# STM32.net
KiCad netlist of a schematic drawn in Altium Designer
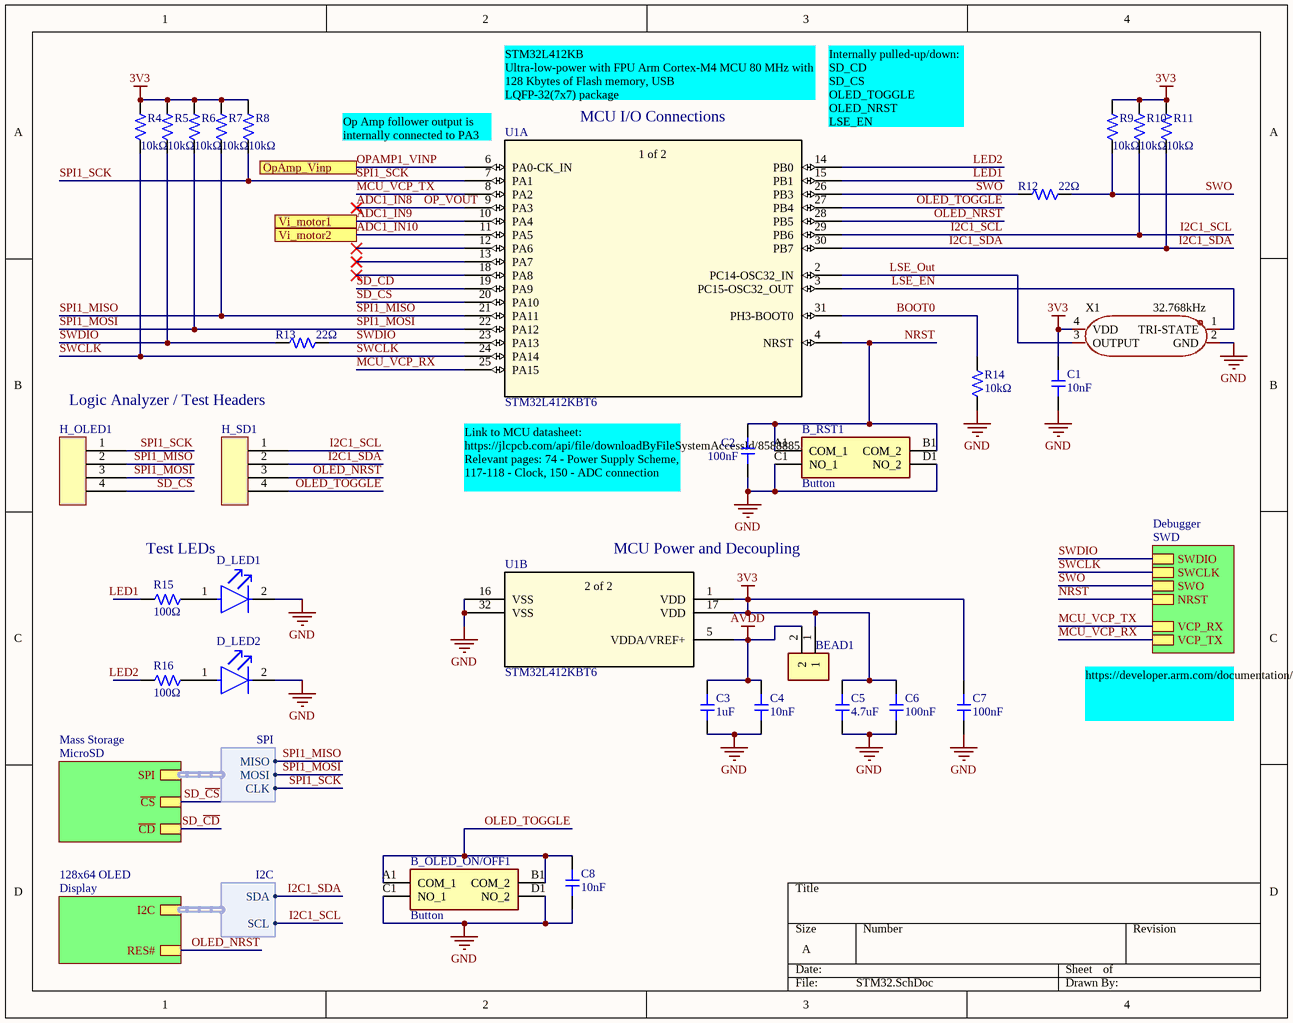
[diagram p0: STM32.SchDoc]

(export (version "E")
  (design (tool "Eeschema 10.0.6"))
  (components
    (comp (ref "BEAD1")
      (value "GZ1608D601TF")
      (footprint "SamacSys:BEADC1608X95N")
      (description "Ferrite Bead")
      (libsource (lib "SamacSys") (part "GZ1608D601TF"))
    )
    (comp (ref "B_OLED_ON/OFF1")
      (value "Button")
      (footprint "SamacSys:TS1187ABAB")
      (fields (field (name "MANUFACTURER_PART_NUMBER") "TS-1187A-B-A-B"))
      (libsource (lib "SamacSys") (part "TS-1187A-B-A-B"))
    )
    (comp (ref "B_RST1")
      (value "Button")
      (footprint "SamacSys:TS1187ABAB")
      (fields (field (name "MANUFACTURER_PART_NUMBER") "TS-1187A-B-A-B"))
      (libsource (lib "SamacSys") (part "TS-1187A-B-A-B"))
    )
    (comp (ref "C1")
      (value "CL05B103KB5NNNC")
      (footprint "CAP-0402")
      (description "Capacitor, Ceramic (MLCC), 10nF, ±10%, 50V, X7R, ±10%, SMD 0402")
      (fields
        (field (name "JLCPCB BASIC PART") "Yes")
        (field (name "CAPACITANCE") "10nF")
        (field (name "JLCPCB PART NUMBER") "C15195")
      )
      (libsource (lib "jlcpcb_2024_10_capacitors_basic") (part "CL05B103KB5NNNC"))
    )
    (comp (ref "C2")
      (value "CL05B104KB54PNC")
      (footprint "CAP-0402")
      (description "Capacitor, Ceramic (MLCC), 100nF, ±10%, 50V, X7R, ±10%, SMD 0402")
      (fields
        (field (name "JLCPCB BASIC PART") "Yes")
        (field (name "CAPACITANCE") "100nF")
        (field (name "JLCPCB PART NUMBER") "C307331")
      )
      (libsource (lib "jlcpcb_2024_10_capacitors_basic") (part "CL05B104KB54PNC"))
    )
    (comp (ref "C3")
      (value "CL05A105KA5NQNC")
      (footprint "CAP-0402")
      (description "Capacitor, Ceramic (MLCC), 1uF, ±10%, 25V, X5R, ±10%, SMD 0402")
      (fields
        (field (name "JLCPCB BASIC PART") "Yes")
        (field (name "CAPACITANCE") "1uF")
        (field (name "JLCPCB PART NUMBER") "C52923")
      )
      (libsource (lib "jlcpcb_2024_10_capacitors_basic") (part "CL05A105KA5NQNC"))
    )
    (comp (ref "C4")
      (value "CL05B103KB5NNNC")
      (footprint "CAP-0402")
      (description "Capacitor, Ceramic (MLCC), 10nF, ±10%, 50V, X7R, ±10%, SMD 0402")
      (fields
        (field (name "JLCPCB BASIC PART") "Yes")
        (field (name "CAPACITANCE") "10nF")
        (field (name "JLCPCB PART NUMBER") "C15195")
      )
      (libsource (lib "jlcpcb_2024_10_capacitors_basic") (part "CL05B103KB5NNNC"))
    )
    (comp (ref "C5")
      (value "CL05A475MP5NRNC")
      (footprint "CAP-0402")
      (description "Capacitor, Ceramic (MLCC), 4.7uF, ±20%, 10V, X5R, ±20%, SMD 0402")
      (fields
        (field (name "JLCPCB BASIC PART") "Yes")
        (field (name "CAPACITANCE") "4.7uF")
        (field (name "JLCPCB PART NUMBER") "C23733")
      )
      (libsource (lib "jlcpcb_2024_10_capacitors_basic") (part "CL05A475MP5NRNC"))
    )
    (comp (ref "C6")
      (value "CL05B104KO5NNNC")
      (footprint "CAP-0402")
      (description "Capacitor, Ceramic (MLCC), 100nF, ±10%, 16V, X7R, ±10%, SMD 0402")
      (fields
        (field (name "JLCPCB BASIC PART") "Yes")
        (field (name "CAPACITANCE") "100nF")
        (field (name "JLCPCB PART NUMBER") "C1525")
      )
      (libsource (lib "jlcpcb_2024_10_capacitors_basic") (part "CL05B104KO5NNNC"))
    )
    (comp (ref "C7")
      (value "CL05B104KO5NNNC")
      (footprint "CAP-0402")
      (description "Capacitor, Ceramic (MLCC), 100nF, ±10%, 16V, X7R, ±10%, SMD 0402")
      (fields
        (field (name "JLCPCB BASIC PART") "Yes")
        (field (name "CAPACITANCE") "100nF")
        (field (name "JLCPCB PART NUMBER") "C1525")
      )
      (libsource (lib "jlcpcb_2024_10_capacitors_basic") (part "CL05B104KO5NNNC"))
    )
    (comp (ref "C8")
      (value "CL05B103KB5NNNC")
      (footprint "CAP-0402")
      (description "Capacitor, Ceramic (MLCC), 10nF, ±10%, 50V, X7R, ±10%, SMD 0402")
      (fields
        (field (name "JLCPCB BASIC PART") "Yes")
        (field (name "CAPACITANCE") "10nF")
        (field (name "JLCPCB PART NUMBER") "C15195")
      )
      (libsource (lib "jlcpcb_2024_10_capacitors_basic") (part "CL05B103KB5NNNC"))
    )
    (comp (ref "D_LED1")
      (value "~")
      (footprint "FP-AP2012EC-MFG")
      (description "LED RED CLEAR SMD")
      (libsource (lib "Red-LED - 01.02.26 - 14") (part "CMP-44529-000070-1"))
    )
    (comp (ref "D_LED2")
      (value "~")
      (footprint "FP-AP2012EC-MFG")
      (description "LED RED CLEAR SMD")
      (libsource (lib "Red-LED - 01.02.26 - 14") (part "ab1c01a81903e929fc6c44469aada92"))
    )
    (comp (ref "H_OLED1")
      (value "4-pin Header")
      (footprint "4-pin Header")
      (description "4-pin Header 0.1mm pitch")
      (libsource (lib "Schlib1") (part "4-pin Header"))
    )
    (comp (ref "H_SD1")
      (value "4-pin Header")
      (footprint "4-pin Header")
      (description "4-pin Header 0.1mm pitch")
      (libsource (lib "Schlib1") (part "4-pin Header"))
    )
    (comp (ref "R4")
      (value "0402WGF1002TCE")
      (footprint "RES-0402")
      (description "Resistor, 10kΩ, ±1%, 62.5mW, 50V, ±100ppm/℃, -55℃~+155℃, SMD 0402")
      (fields
        (field (name "MANUFACTURER") "Uniroyal")
        (field (name "JLCPCB PART NUMBER") "C25744")
        (field (name "RESISTANCE") "10kΩ")
      )
      (libsource (lib "jlcpcb_2024_10_resistors_basic") (part "0402WGF1002TCE"))
    )
    (comp (ref "R5")
      (value "0402WGF1002TCE")
      (footprint "RES-0402")
      (description "Resistor, 10kΩ, ±1%, 62.5mW, 50V, ±100ppm/℃, -55℃~+155℃, SMD 0402")
      (fields
        (field (name "MANUFACTURER") "Uniroyal")
        (field (name "JLCPCB PART NUMBER") "C25744")
        (field (name "RESISTANCE") "10kΩ")
      )
      (libsource (lib "jlcpcb_2024_10_resistors_basic") (part "0402WGF1002TCE"))
    )
    (comp (ref "R6")
      (value "0402WGF1002TCE")
      (footprint "RES-0402")
      (description "Resistor, 10kΩ, ±1%, 62.5mW, 50V, ±100ppm/℃, -55℃~+155℃, SMD 0402")
      (fields
        (field (name "MANUFACTURER") "Uniroyal")
        (field (name "JLCPCB PART NUMBER") "C25744")
        (field (name "RESISTANCE") "10kΩ")
      )
      (libsource (lib "jlcpcb_2024_10_resistors_basic") (part "0402WGF1002TCE"))
    )
    (comp (ref "R7")
      (value "0402WGF1002TCE")
      (footprint "RES-0402")
      (description "Resistor, 10kΩ, ±1%, 62.5mW, 50V, ±100ppm/℃, -55℃~+155℃, SMD 0402")
      (fields
        (field (name "MANUFACTURER") "Uniroyal")
        (field (name "JLCPCB PART NUMBER") "C25744")
        (field (name "RESISTANCE") "10kΩ")
      )
      (libsource (lib "jlcpcb_2024_10_resistors_basic") (part "0402WGF1002TCE"))
    )
    (comp (ref "R8")
      (value "0402WGF1002TCE")
      (footprint "RES-0402")
      (description "Resistor, 10kΩ, ±1%, 62.5mW, 50V, ±100ppm/℃, -55℃~+155℃, SMD 0402")
      (fields
        (field (name "MANUFACTURER") "Uniroyal")
        (field (name "JLCPCB PART NUMBER") "C25744")
        (field (name "RESISTANCE") "10kΩ")
      )
      (libsource (lib "jlcpcb_2024_10_resistors_basic") (part "0402WGF1002TCE"))
    )
    (comp (ref "R9")
      (value "0402WGF1002TCE")
      (footprint "RES-0402")
      (description "Resistor, 10kΩ, ±1%, 62.5mW, 50V, ±100ppm/℃, -55℃~+155℃, SMD 0402")
      (fields
        (field (name "MANUFACTURER") "Uniroyal")
        (field (name "JLCPCB PART NUMBER") "C25744")
        (field (name "RESISTANCE") "10kΩ")
      )
      (libsource (lib "jlcpcb_2024_10_resistors_basic") (part "0402WGF1002TCE"))
    )
    (comp (ref "R10")
      (value "0402WGF1002TCE")
      (footprint "RES-0402")
      (description "Resistor, 10kΩ, ±1%, 62.5mW, 50V, ±100ppm/℃, -55℃~+155℃, SMD 0402")
      (fields
        (field (name "MANUFACTURER") "Uniroyal")
        (field (name "JLCPCB PART NUMBER") "C25744")
        (field (name "RESISTANCE") "10kΩ")
      )
      (libsource (lib "jlcpcb_2024_10_resistors_basic") (part "0402WGF1002TCE"))
    )
    (comp (ref "R11")
      (value "0402WGF1002TCE")
      (footprint "RES-0402")
      (description "Resistor, 10kΩ, ±1%, 62.5mW, 50V, ±100ppm/℃, -55℃~+155℃, SMD 0402")
      (fields
        (field (name "MANUFACTURER") "Uniroyal")
        (field (name "JLCPCB PART NUMBER") "C25744")
        (field (name "RESISTANCE") "10kΩ")
      )
      (libsource (lib "jlcpcb_2024_10_resistors_basic") (part "0402WGF1002TCE"))
    )
    (comp (ref "R12")
      (value "0402WGF220JTCE")
      (footprint "RES-0402")
      (description "Resistor, 22Ω, ±1%, 62.5mW, 50V, ±200ppm/℃, -55℃~+155℃, SMD 0402")
      (fields
        (field (name "MANUFACTURER") "Uniroyal")
        (field (name "JLCPCB PART NUMBER") "C25092")
        (field (name "RESISTANCE") "22Ω")
      )
      (libsource (lib "jlcpcb_2024_10_resistors_basic") (part "0402WGF220JTCE"))
    )
    (comp (ref "R13")
      (value "0402WGF220JTCE")
      (footprint "RES-0402")
      (description "Resistor, 22Ω, ±1%, 62.5mW, 50V, ±200ppm/℃, -55℃~+155℃, SMD 0402")
      (fields
        (field (name "MANUFACTURER") "Uniroyal")
        (field (name "JLCPCB PART NUMBER") "C25092")
        (field (name "RESISTANCE") "22Ω")
      )
      (libsource (lib "jlcpcb_2024_10_resistors_basic") (part "0402WGF220JTCE"))
    )
    (comp (ref "R14")
      (value "0402WGF1002TCE")
      (footprint "RES-0402")
      (description "Resistor, 10kΩ, ±1%, 62.5mW, 50V, ±100ppm/℃, -55℃~+155℃, SMD 0402")
      (fields
        (field (name "MANUFACTURER") "Uniroyal")
        (field (name "JLCPCB PART NUMBER") "C25744")
        (field (name "RESISTANCE") "10kΩ")
      )
      (libsource (lib "jlcpcb_2024_10_resistors_basic") (part "0402WGF1002TCE"))
    )
    (comp (ref "R15")
      (value "0402WGF1000TCE")
      (footprint "RES-0402")
      (description "Resistor, 100Ω, ±1%, 62.5mW, 50V, ±200ppm/℃, -55℃~+155℃, SMD 0402")
      (fields
        (field (name "MANUFACTURER") "Uniroyal")
        (field (name "JLCPCB PART NUMBER") "C25076")
        (field (name "RESISTANCE") "100Ω")
      )
      (libsource (lib "jlcpcb_2024_10_resistors_basic") (part "0402WGF1000TCE"))
    )
    (comp (ref "R16")
      (value "0402WGF1000TCE")
      (footprint "RES-0402")
      (description "Resistor, 100Ω, ±1%, 62.5mW, 50V, ±200ppm/℃, -55℃~+155℃, SMD 0402")
      (fields
        (field (name "MANUFACTURER") "Uniroyal")
        (field (name "JLCPCB PART NUMBER") "C25076")
        (field (name "RESISTANCE") "100Ω")
      )
      (libsource (lib "jlcpcb_2024_10_resistors_basic") (part "0402WGF1000TCE"))
    )
    (comp (ref "U1")
      (value "STM32L412KBT6")
      (footprint "LQFP-32")
      (description "No Description Available")
      (libsource (lib "STM32L412KBT6") (part "STM32L412KBT6"))
    )
    (comp (ref "X1")
      (value "32.768kHz")
      (footprint "OSC-SMD_4P-L3.2-W2.5-BL:OSC-SMD_4P-L3.2-W2.5-BL")
      (fields
        (field (name "MANUFACTURER") "SCTF(星通时频)")
        (field (name "MANUFACTURER PART") "SX3M32.768KM20F30TNN")
      )
      (libsource (lib "SX3M32.768KM20F30TNN1_SX3M32.768KM20F30TNN") (part "SX3M32.768KM20F30TNN"))
    )
  )
  (nets
    (net (code "4") (name "/ADC1_IN8") (class "Default")
      (node (ref "U1") (pin "9") (pinfunction "PA3_9") (pintype "bidirectional+no_connect"))
    )
    (net (code "5") (name "/ADC1_IN9") (class "Default")
      (node (ref "U1") (pin "10") (pinfunction "PA4_10") (pintype "bidirectional"))
    )
    (net (code "6") (name "/ADC1_IN10") (class "Default")
      (node (ref "U1") (pin "11") (pinfunction "PA5_11") (pintype "bidirectional"))
    )
    (net (code "7") (name "/BOOT0") (class "Default")
      (node (ref "R14") (pin "2") (pinfunction "2_2") (pintype "passive"))
      (node (ref "U1") (pin "31") (pinfunction "PH3-BOOT0_31") (pintype "bidirectional"))
    )
    (net (code "8") (name "/I2C1_SCL") (class "Default")
      (node (ref "H_SD1") (pin "1") (pinfunction "1_1") (pintype "passive"))
      (node (ref "R10") (pin "1") (pinfunction "1_1") (pintype "passive"))
      (node (ref "U1") (pin "29") (pinfunction "PB6_29") (pintype "bidirectional"))
    )
    (net (code "9") (name "/I2C1_SDA") (class "Default")
      (node (ref "H_SD1") (pin "2") (pinfunction "2_2") (pintype "passive"))
      (node (ref "R11") (pin "1") (pinfunction "1_1") (pintype "passive"))
      (node (ref "U1") (pin "30") (pinfunction "PB7_30") (pintype "bidirectional"))
    )
    (net (code "10") (name "/LED1") (class "Default")
      (node (ref "R15") (pin "1") (pinfunction "1_1") (pintype "passive"))
      (node (ref "U1") (pin "15") (pinfunction "PB1_15") (pintype "bidirectional"))
    )
    (net (code "11") (name "/LED2") (class "Default")
      (node (ref "R16") (pin "1") (pinfunction "1_1") (pintype "passive"))
      (node (ref "U1") (pin "14") (pinfunction "PB0_14") (pintype "bidirectional"))
    )
    (net (code "12") (name "/LSE_EN") (class "Default")
      (node (ref "U1") (pin "3") (pinfunction "PC15-OSC32_OUT_3") (pintype "bidirectional"))
      (node (ref "X1") (pin "1") (pinfunction "TRI-STATE_1") (pintype "passive"))
    )
    (net (code "13") (name "/LSE_Out") (class "Default")
      (node (ref "U1") (pin "2") (pinfunction "PC14-OSC32_IN_2") (pintype "bidirectional"))
      (node (ref "X1") (pin "3") (pinfunction "OUTPUT_3") (pintype "passive"))
    )
    (net (code "14") (name "/MCU_VCP_RX") (class "Default")
      (node (ref "U1") (pin "25") (pinfunction "PA15_25") (pintype "bidirectional"))
    )
    (net (code "15") (name "/MCU_VCP_TX") (class "Default")
      (node (ref "U1") (pin "8") (pinfunction "PA2_8") (pintype "bidirectional"))
    )
    (net (code "16") (name "/NRST") (class "Default")
      (node (ref "B_RST1") (pin "A1") (pinfunction "COM_1_A1") (pintype "passive"))
      (node (ref "B_RST1") (pin "B1") (pinfunction "COM_2_B1") (pintype "passive"))
      (node (ref "C2") (pin "2") (pinfunction "2_2") (pintype "passive"))
      (node (ref "U1") (pin "4") (pinfunction "NRST_4") (pintype "bidirectional"))
    )
    (net (code "17") (name "/OLED_NRST") (class "Default")
      (node (ref "H_SD1") (pin "3") (pinfunction "3_3") (pintype "passive"))
      (node (ref "U1") (pin "28") (pinfunction "PB5_28") (pintype "bidirectional"))
    )
    (net (code "18") (name "/OLED_TOGGLE") (class "Default")
      (node (ref "B_OLED_ON/OFF1") (pin "A1") (pinfunction "COM_1_A1") (pintype "passive"))
      (node (ref "B_OLED_ON/OFF1") (pin "B1") (pinfunction "COM_2_B1") (pintype "passive"))
      (node (ref "C8") (pin "2") (pinfunction "2_2") (pintype "passive"))
      (node (ref "H_SD1") (pin "4") (pinfunction "4_4") (pintype "passive"))
      (node (ref "U1") (pin "27") (pinfunction "PB4_27") (pintype "bidirectional"))
    )
    (net (code "19") (name "/OPAMP1_VINP") (class "Default")
      (node (ref "U1") (pin "6") (pinfunction "PA0-CK_IN_6") (pintype "bidirectional"))
    )
    (net (code "20") (name "/SD_~{CD}") (class "Default")
      (node (ref "U1") (pin "19") (pinfunction "PA9_19") (pintype "bidirectional"))
    )
    (net (code "21") (name "/SD_~{CS}") (class "Default")
      (node (ref "H_OLED1") (pin "4") (pinfunction "4_4") (pintype "passive"))
      (node (ref "U1") (pin "20") (pinfunction "PA10_20") (pintype "bidirectional"))
    )
    (net (code "22") (name "/SPI1_MISO") (class "Default")
      (node (ref "H_OLED1") (pin "2") (pinfunction "2_2") (pintype "passive"))
      (node (ref "R7") (pin "1") (pinfunction "1_1") (pintype "passive"))
      (node (ref "U1") (pin "21") (pinfunction "PA11_21") (pintype "bidirectional"))
    )
    (net (code "23") (name "/SPI1_MOSI") (class "Default")
      (node (ref "H_OLED1") (pin "3") (pinfunction "3_3") (pintype "passive"))
      (node (ref "R6") (pin "1") (pinfunction "1_1") (pintype "passive"))
      (node (ref "U1") (pin "22") (pinfunction "PA12_22") (pintype "bidirectional"))
    )
    (net (code "24") (name "/SPI1_SCK") (class "Default")
      (node (ref "H_OLED1") (pin "1") (pinfunction "1_1") (pintype "passive"))
      (node (ref "R8") (pin "1") (pinfunction "1_1") (pintype "passive"))
      (node (ref "U1") (pin "7") (pinfunction "PA1_7") (pintype "bidirectional"))
    )
    (net (code "25") (name "/SWCLK") (class "Default")
      (node (ref "R4") (pin "1") (pinfunction "1_1") (pintype "passive"))
      (node (ref "U1") (pin "24") (pinfunction "PA14_24") (pintype "bidirectional"))
    )
    (net (code "26") (name "/SWDIO") (class "Default")
      (node (ref "R13") (pin "1") (pinfunction "1_1") (pintype "passive"))
      (node (ref "R13") (pin "2") (pinfunction "2_2") (pintype "passive"))
      (node (ref "R5") (pin "1") (pinfunction "1_1") (pintype "passive"))
      (node (ref "U1") (pin "23") (pinfunction "PA13_23") (pintype "bidirectional"))
    )
    (net (code "27") (name "/SWO") (class "Default")
      (node (ref "R12") (pin "1") (pinfunction "1_1") (pintype "passive"))
      (node (ref "R12") (pin "2") (pinfunction "2_2") (pintype "passive"))
      (node (ref "R9") (pin "1") (pinfunction "1_1") (pintype "passive"))
      (node (ref "U1") (pin "26") (pinfunction "PB3_26") (pintype "bidirectional"))
    )
    (net (code "30") (name "3V3") (class "Default")
      (node (ref "BEAD1") (pin "1") (pinfunction "1_1") (pintype "passive"))
      (node (ref "C1") (pin "2") (pinfunction "2_2") (pintype "passive"))
      (node (ref "C5") (pin "2") (pinfunction "2_2") (pintype "passive"))
      (node (ref "C6") (pin "2") (pinfunction "2_2") (pintype "passive"))
      (node (ref "C7") (pin "2") (pinfunction "2_2") (pintype "passive"))
      (node (ref "R10") (pin "2") (pinfunction "2_2") (pintype "passive"))
      (node (ref "R11") (pin "2") (pinfunction "2_2") (pintype "passive"))
      (node (ref "R4") (pin "2") (pinfunction "2_2") (pintype "passive"))
      (node (ref "R5") (pin "2") (pinfunction "2_2") (pintype "passive"))
      (node (ref "R6") (pin "2") (pinfunction "2_2") (pintype "passive"))
      (node (ref "R7") (pin "2") (pinfunction "2_2") (pintype "passive"))
      (node (ref "R8") (pin "2") (pinfunction "2_2") (pintype "passive"))
      (node (ref "R9") (pin "2") (pinfunction "2_2") (pintype "passive"))
      (node (ref "U1") (pin "1") (pinfunction "VDD_1") (pintype "power_in"))
      (node (ref "U1") (pin "17") (pinfunction "VDD_17") (pintype "power_in"))
      (node (ref "X1") (pin "4") (pinfunction "VDD_4") (pintype "passive"))
    )
    (net (code "31") (name "AVDD") (class "Default")
      (node (ref "BEAD1") (pin "2") (pinfunction "2_2") (pintype "passive"))
      (node (ref "C3") (pin "2") (pinfunction "2_2") (pintype "passive"))
      (node (ref "C4") (pin "2") (pinfunction "2_2") (pintype "passive"))
      (node (ref "U1") (pin "5") (pinfunction "VDDA/VREF+_5") (pintype "power_in"))
    )
    (net (code "32") (name "GND") (class "Default")
      (node (ref "B_OLED_ON/OFF1") (pin "C1") (pinfunction "NO_1_C1") (pintype "passive"))
      (node (ref "B_OLED_ON/OFF1") (pin "D1") (pinfunction "NO_2_D1") (pintype "passive"))
      (node (ref "B_RST1") (pin "C1") (pinfunction "NO_1_C1") (pintype "passive"))
      (node (ref "B_RST1") (pin "D1") (pinfunction "NO_2_D1") (pintype "passive"))
      (node (ref "C1") (pin "1") (pinfunction "1_1") (pintype "passive"))
      (node (ref "C2") (pin "1") (pinfunction "1_1") (pintype "passive"))
      (node (ref "C3") (pin "1") (pinfunction "1_1") (pintype "passive"))
      (node (ref "C4") (pin "1") (pinfunction "1_1") (pintype "passive"))
      (node (ref "C5") (pin "1") (pinfunction "1_1") (pintype "passive"))
      (node (ref "C6") (pin "1") (pinfunction "1_1") (pintype "passive"))
      (node (ref "C7") (pin "1") (pinfunction "1_1") (pintype "passive"))
      (node (ref "C8") (pin "1") (pinfunction "1_1") (pintype "passive"))
      (node (ref "D_LED1") (pin "2") (pinfunction "C_2") (pintype "passive"))
      (node (ref "D_LED2") (pin "2") (pinfunction "C_2") (pintype "passive"))
      (node (ref "R14") (pin "1") (pinfunction "1_1") (pintype "passive"))
      (node (ref "U1") (pin "16") (pinfunction "VSS_16") (pintype "power_in"))
      (node (ref "U1") (pin "32") (pinfunction "VSS_32") (pintype "power_in"))
      (node (ref "X1") (pin "2") (pinfunction "GND_2") (pintype "passive"))
    )
    (net (code "33") (name "Net-(D_LED1-A)") (class "Default")
      (node (ref "D_LED1") (pin "1") (pinfunction "A_1") (pintype "passive"))
      (node (ref "R15") (pin "2") (pinfunction "2_2") (pintype "passive"))
    )
    (net (code "34") (name "Net-(D_LED2-A)") (class "Default")
      (node (ref "D_LED2") (pin "1") (pinfunction "A_1") (pintype "passive"))
      (node (ref "R16") (pin "2") (pinfunction "2_2") (pintype "passive"))
    )
    (net (code "35") (name "unconnected-(U1A-PA6-Pad12)") (class "Default")
      (node (ref "U1") (pin "12") (pinfunction "PA6_12") (pintype "bidirectional+no_connect"))
    )
    (net (code "36") (name "unconnected-(U1A-PA7-Pad13)") (class "Default")
      (node (ref "U1") (pin "13") (pinfunction "PA7_13") (pintype "bidirectional+no_connect"))
    )
    (net (code "37") (name "unconnected-(U1A-PA8-Pad18)") (class "Default")
      (node (ref "U1") (pin "18") (pinfunction "PA8_18") (pintype "bidirectional+no_connect"))
    )
  )
)
